# Power.net
KiCad netlist of a schematic drawn in Altium Designer
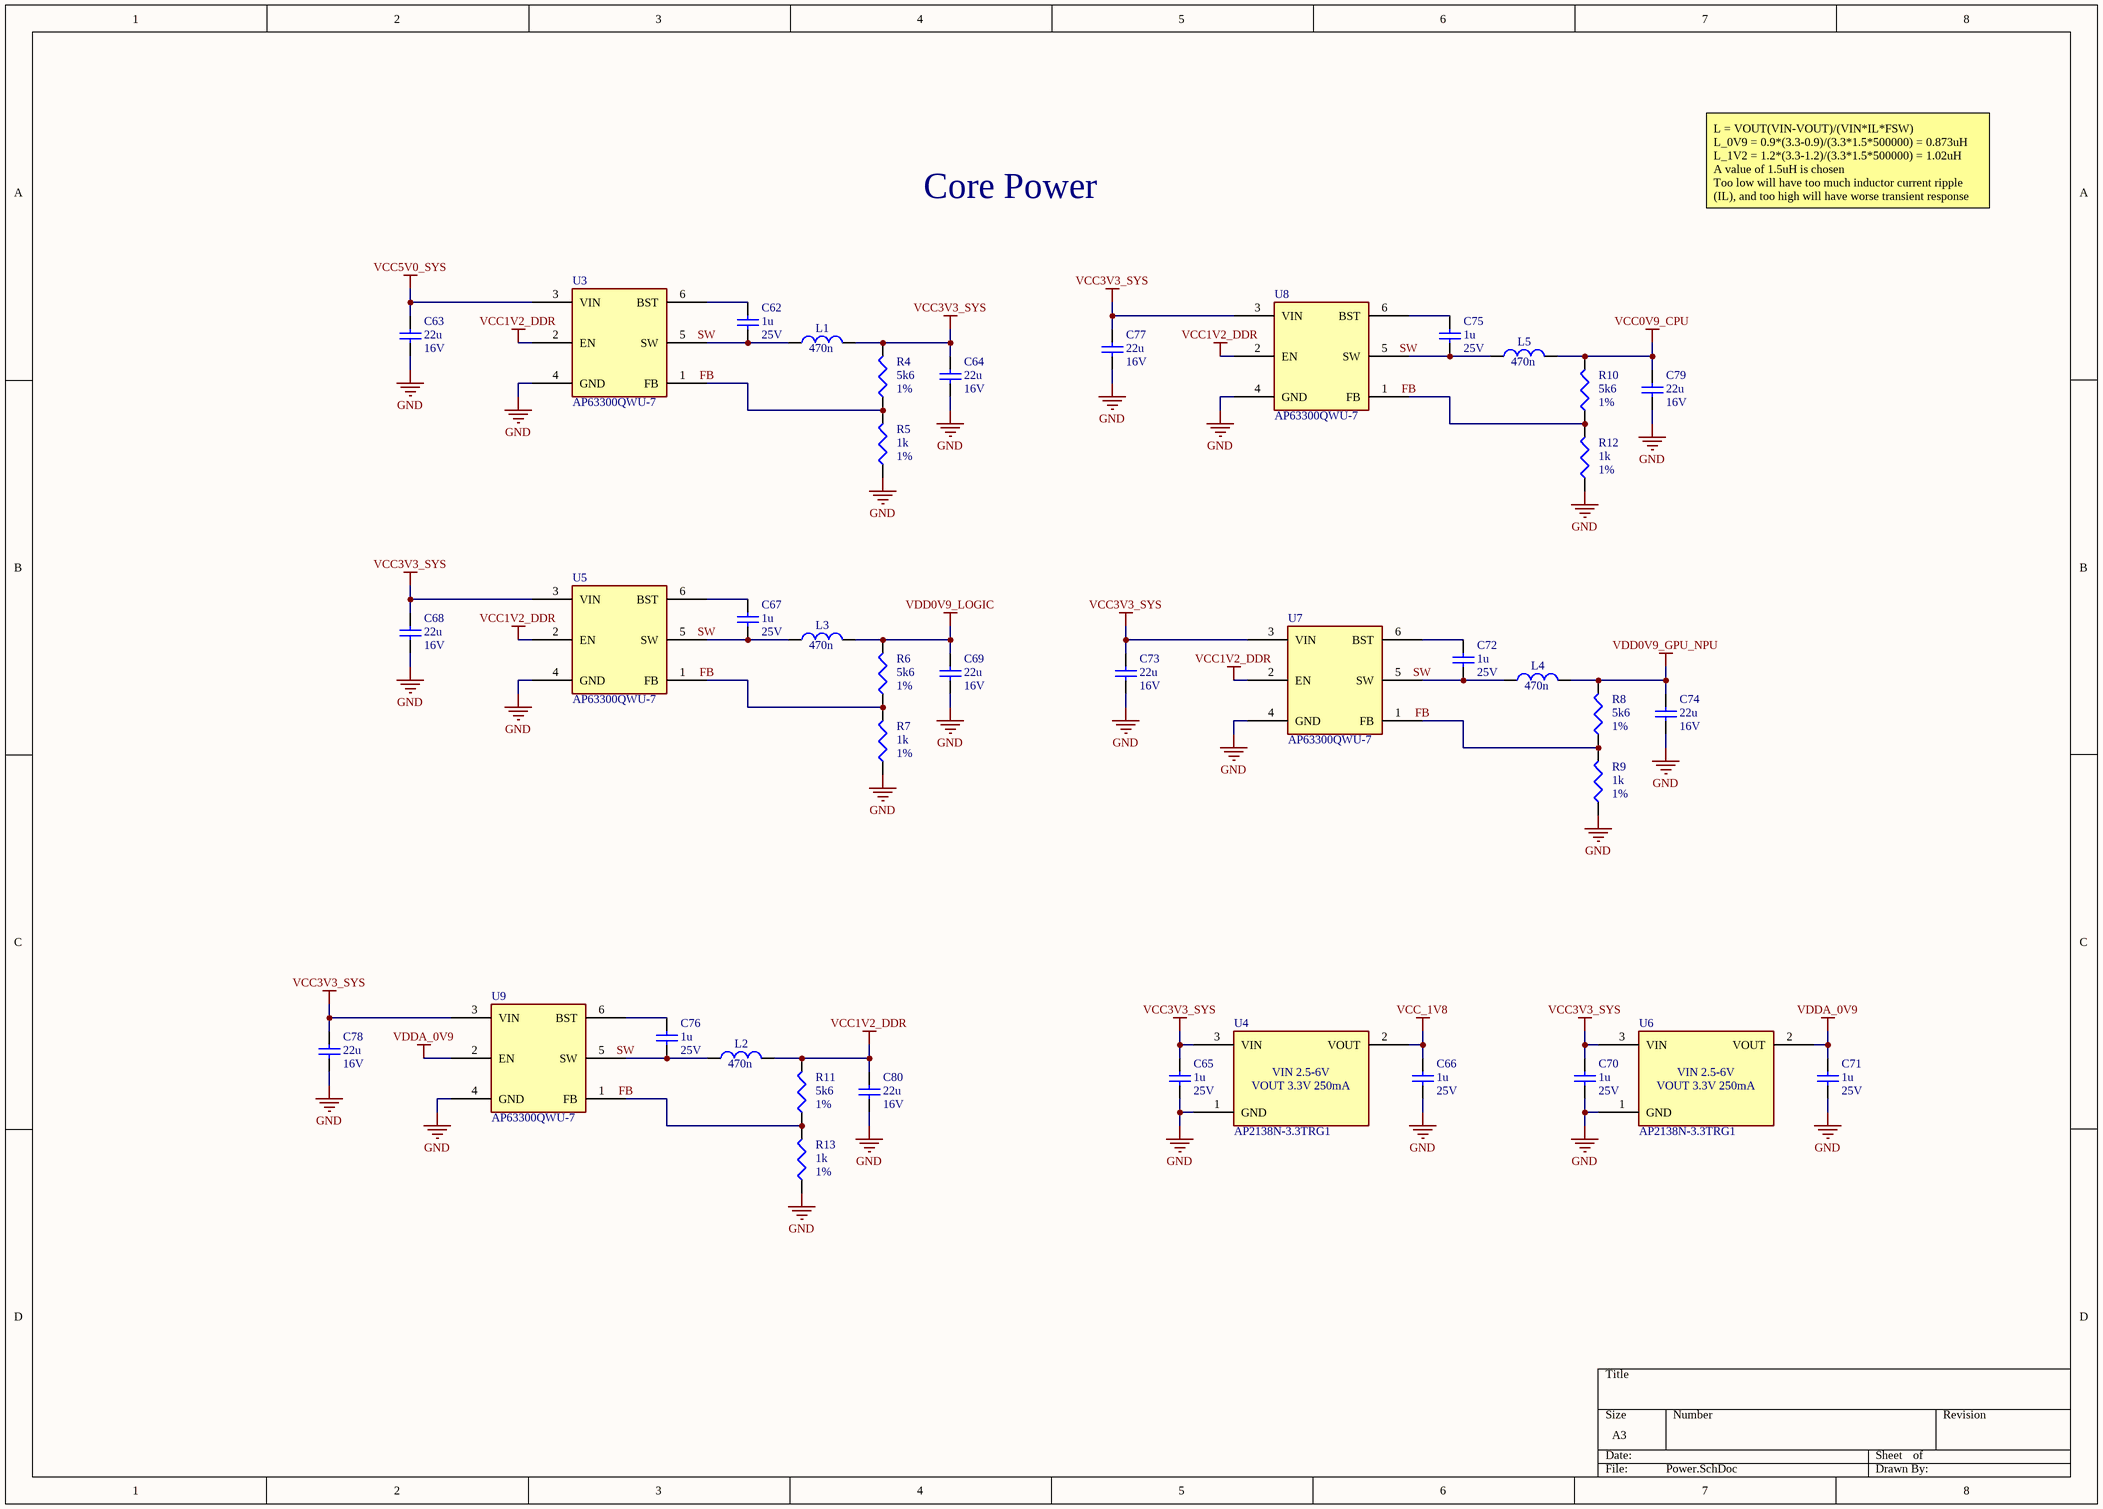
[diagram p0: Power.SchDoc]

(export (version "E")
  (design (tool "Eeschema 10.0.6"))
  (components
    (comp (ref "C62")
      (value "1u")
      (footprint "GRM155R61E105KA12D")
      (description "CAP 1U 25V X5R 0402")
      (fields (field (name "VOLTAGE") "25V") (field (name "Comment") "GRM155R61E105KA12D"))
      (libsource (lib "PersonalAltiumLibrary") (part "GRM155R61E105KA12D"))
    )
    (comp (ref "C63")
      (value "22u")
      (footprint "GRM188R61C226ME01D")
      (description "CAP 22U 16V X5R 0603")
      (fields (field (name "VOLTAGE") "16V") (field (name "Comment") "GRM188R61C226ME01D"))
      (libsource (lib "PersonalAltiumLibrary") (part "GRM188R61C226ME01D"))
    )
    (comp (ref "C64")
      (value "22u")
      (footprint "GRM188R61C226ME01D")
      (description "CAP 22U 16V X5R 0603")
      (fields (field (name "VOLTAGE") "16V") (field (name "Comment") "GRM188R61C226ME01D"))
      (libsource (lib "PersonalAltiumLibrary") (part "GRM188R61C226ME01D"))
    )
    (comp (ref "C65")
      (value "1u")
      (footprint "GRM155R61E105KA12D")
      (description "CAP 1U 25V X5R 0402")
      (fields (field (name "VOLTAGE") "25V") (field (name "Comment") "GRM155R61E105KA12D"))
      (libsource (lib "PersonalAltiumLibrary") (part "GRM155R61E105KA12D"))
    )
    (comp (ref "C66")
      (value "1u")
      (footprint "GRM155R61E105KA12D")
      (description "CAP 1U 25V X5R 0402")
      (fields (field (name "VOLTAGE") "25V") (field (name "Comment") "GRM155R61E105KA12D"))
      (libsource (lib "PersonalAltiumLibrary") (part "GRM155R61E105KA12D"))
    )
    (comp (ref "C67")
      (value "1u")
      (footprint "GRM155R61E105KA12D")
      (description "CAP 1U 25V X5R 0402")
      (fields (field (name "VOLTAGE") "25V") (field (name "Comment") "GRM155R61E105KA12D"))
      (libsource (lib "PersonalAltiumLibrary") (part "GRM155R61E105KA12D"))
    )
    (comp (ref "C68")
      (value "22u")
      (footprint "GRM188R61C226ME01D")
      (description "CAP 22U 16V X5R 0603")
      (fields (field (name "VOLTAGE") "16V") (field (name "Comment") "GRM188R61C226ME01D"))
      (libsource (lib "PersonalAltiumLibrary") (part "GRM188R61C226ME01D"))
    )
    (comp (ref "C69")
      (value "22u")
      (footprint "GRM188R61C226ME01D")
      (description "CAP 22U 16V X5R 0603")
      (fields (field (name "VOLTAGE") "16V") (field (name "Comment") "GRM188R61C226ME01D"))
      (libsource (lib "PersonalAltiumLibrary") (part "GRM188R61C226ME01D"))
    )
    (comp (ref "C70")
      (value "1u")
      (footprint "GRM155R61E105KA12D")
      (description "CAP 1U 25V X5R 0402")
      (fields (field (name "VOLTAGE") "25V") (field (name "Comment") "GRM155R61E105KA12D"))
      (libsource (lib "PersonalAltiumLibrary") (part "GRM155R61E105KA12D"))
    )
    (comp (ref "C71")
      (value "1u")
      (footprint "GRM155R61E105KA12D")
      (description "CAP 1U 25V X5R 0402")
      (fields (field (name "VOLTAGE") "25V") (field (name "Comment") "GRM155R61E105KA12D"))
      (libsource (lib "PersonalAltiumLibrary") (part "GRM155R61E105KA12D"))
    )
    (comp (ref "C72")
      (value "1u")
      (footprint "GRM155R61E105KA12D")
      (description "CAP 1U 25V X5R 0402")
      (fields (field (name "VOLTAGE") "25V") (field (name "Comment") "GRM155R61E105KA12D"))
      (libsource (lib "PersonalAltiumLibrary") (part "GRM155R61E105KA12D"))
    )
    (comp (ref "C73")
      (value "22u")
      (footprint "GRM188R61C226ME01D")
      (description "CAP 22U 16V X5R 0603")
      (fields (field (name "VOLTAGE") "16V") (field (name "Comment") "GRM188R61C226ME01D"))
      (libsource (lib "PersonalAltiumLibrary") (part "GRM188R61C226ME01D"))
    )
    (comp (ref "C74")
      (value "22u")
      (footprint "GRM188R61C226ME01D")
      (description "CAP 22U 16V X5R 0603")
      (fields (field (name "VOLTAGE") "16V") (field (name "Comment") "GRM188R61C226ME01D"))
      (libsource (lib "PersonalAltiumLibrary") (part "GRM188R61C226ME01D"))
    )
    (comp (ref "C75")
      (value "1u")
      (footprint "GRM155R61E105KA12D")
      (description "CAP 1U 25V X5R 0402")
      (fields (field (name "VOLTAGE") "25V") (field (name "Comment") "GRM155R61E105KA12D"))
      (libsource (lib "PersonalAltiumLibrary") (part "GRM155R61E105KA12D"))
    )
    (comp (ref "C76")
      (value "1u")
      (footprint "GRM155R61E105KA12D")
      (description "CAP 1U 25V X5R 0402")
      (fields (field (name "VOLTAGE") "25V") (field (name "Comment") "GRM155R61E105KA12D"))
      (libsource (lib "PersonalAltiumLibrary") (part "GRM155R61E105KA12D"))
    )
    (comp (ref "C77")
      (value "22u")
      (footprint "GRM188R61C226ME01D")
      (description "CAP 22U 16V X5R 0603")
      (fields (field (name "VOLTAGE") "16V") (field (name "Comment") "GRM188R61C226ME01D"))
      (libsource (lib "PersonalAltiumLibrary") (part "GRM188R61C226ME01D"))
    )
    (comp (ref "C78")
      (value "22u")
      (footprint "GRM188R61C226ME01D")
      (description "CAP 22U 16V X5R 0603")
      (fields (field (name "VOLTAGE") "16V") (field (name "Comment") "GRM188R61C226ME01D"))
      (libsource (lib "PersonalAltiumLibrary") (part "GRM188R61C226ME01D"))
    )
    (comp (ref "C79")
      (value "22u")
      (footprint "GRM188R61C226ME01D")
      (description "CAP 22U 16V X5R 0603")
      (fields (field (name "VOLTAGE") "16V") (field (name "Comment") "GRM188R61C226ME01D"))
      (libsource (lib "PersonalAltiumLibrary") (part "GRM188R61C226ME01D"))
    )
    (comp (ref "C80")
      (value "22u")
      (footprint "GRM188R61C226ME01D")
      (description "CAP 22U 16V X5R 0603")
      (fields (field (name "VOLTAGE") "16V") (field (name "Comment") "GRM188R61C226ME01D"))
      (libsource (lib "PersonalAltiumLibrary") (part "GRM188R61C226ME01D"))
    )
    (comp (ref "L1")
      (value "470n")
      (footprint "DFE322520FD-1R5M")
      (description "IND 1.5U 6A 1210")
      (fields (field (name "Comment") "DFE322520FD-1R5M"))
      (libsource (lib "PersonalAltiumLibrary") (part "DFE322520FD-1R5M"))
    )
    (comp (ref "L2")
      (value "470n")
      (footprint "DFE322520FD-1R5M")
      (description "IND 1.5U 6A 1210")
      (fields (field (name "Comment") "DFE322520FD-1R5M"))
      (libsource (lib "PersonalAltiumLibrary") (part "DFE322520FD-1R5M"))
    )
    (comp (ref "L3")
      (value "470n")
      (footprint "DFE322520FD-1R5M")
      (description "IND 1.5U 6A 1210")
      (fields (field (name "Comment") "DFE322520FD-1R5M"))
      (libsource (lib "PersonalAltiumLibrary") (part "DFE322520FD-1R5M"))
    )
    (comp (ref "L4")
      (value "470n")
      (footprint "DFE322520FD-1R5M")
      (description "IND 1.5U 6A 1210")
      (fields (field (name "Comment") "DFE322520FD-1R5M"))
      (libsource (lib "PersonalAltiumLibrary") (part "DFE322520FD-1R5M"))
    )
    (comp (ref "L5")
      (value "470n")
      (footprint "DFE322520FD-1R5M")
      (description "IND 1.5U 6A 1210")
      (fields (field (name "Comment") "DFE322520FD-1R5M"))
      (libsource (lib "PersonalAltiumLibrary") (part "DFE322520FD-1R5M"))
    )
    (comp (ref "R4")
      (value "5k6")
      (footprint "RC0402FR-075K6L")
      (description "RES 5.6k 1% 62.5mW 0402")
      (fields (field (name "TOLERANCE") "1%") (field (name "Comment") "RC0402FR-075K6L"))
      (libsource (lib "PersonalAltiumLibrary") (part "RC0402FR-075K6L"))
    )
    (comp (ref "R5")
      (value "1k")
      (footprint "RC0402FR-071KL")
      (description "RES 1k 1% 62.5mW 0402")
      (fields (field (name "TOLERANCE") "1%") (field (name "Comment") "RC0402FR-071KL"))
      (libsource (lib "PersonalAltiumLibrary") (part "RC0402FR-071KL"))
    )
    (comp (ref "R6")
      (value "5k6")
      (footprint "RC0402FR-075K6L")
      (description "RES 5.6k 1% 62.5mW 0402")
      (fields (field (name "TOLERANCE") "1%") (field (name "Comment") "RC0402FR-075K6L"))
      (libsource (lib "PersonalAltiumLibrary") (part "RC0402FR-075K6L"))
    )
    (comp (ref "R7")
      (value "1k")
      (footprint "RC0402FR-071KL")
      (description "RES 1k 1% 62.5mW 0402")
      (fields (field (name "TOLERANCE") "1%") (field (name "Comment") "RC0402FR-071KL"))
      (libsource (lib "PersonalAltiumLibrary") (part "RC0402FR-071KL"))
    )
    (comp (ref "R8")
      (value "5k6")
      (footprint "RC0402FR-075K6L")
      (description "RES 5.6k 1% 62.5mW 0402")
      (fields (field (name "TOLERANCE") "1%") (field (name "Comment") "RC0402FR-075K6L"))
      (libsource (lib "PersonalAltiumLibrary") (part "RC0402FR-075K6L"))
    )
    (comp (ref "R9")
      (value "1k")
      (footprint "RC0402FR-071KL")
      (description "RES 1k 1% 62.5mW 0402")
      (fields (field (name "TOLERANCE") "1%") (field (name "Comment") "RC0402FR-071KL"))
      (libsource (lib "PersonalAltiumLibrary") (part "RC0402FR-071KL"))
    )
    (comp (ref "R10")
      (value "5k6")
      (footprint "RC0402FR-075K6L")
      (description "RES 5.6k 1% 62.5mW 0402")
      (fields (field (name "TOLERANCE") "1%") (field (name "Comment") "RC0402FR-075K6L"))
      (libsource (lib "PersonalAltiumLibrary") (part "RC0402FR-075K6L"))
    )
    (comp (ref "R11")
      (value "5k6")
      (footprint "RC0402FR-075K6L")
      (description "RES 5.6k 1% 62.5mW 0402")
      (fields (field (name "TOLERANCE") "1%") (field (name "Comment") "RC0402FR-075K6L"))
      (libsource (lib "PersonalAltiumLibrary") (part "RC0402FR-075K6L"))
    )
    (comp (ref "R12")
      (value "1k")
      (footprint "RC0402FR-071KL")
      (description "RES 1k 1% 62.5mW 0402")
      (fields (field (name "TOLERANCE") "1%") (field (name "Comment") "RC0402FR-071KL"))
      (libsource (lib "PersonalAltiumLibrary") (part "RC0402FR-071KL"))
    )
    (comp (ref "R13")
      (value "1k")
      (footprint "RC0402FR-071KL")
      (description "RES 1k 1% 62.5mW 0402")
      (fields (field (name "TOLERANCE") "1%") (field (name "Comment") "RC0402FR-071KL"))
      (libsource (lib "PersonalAltiumLibrary") (part "RC0402FR-071KL"))
    )
    (comp (ref "U3")
      (value "AP63300QWU-7")
      (footprint "AP63300QWU-7")
      (description "BUCK 3A")
      (libsource (lib "PersonalAltiumLibrary") (part "AP63300QWU-7"))
    )
    (comp (ref "U4")
      (value "AP2138N-3.3TRG1")
      (footprint "AP2138N-3.3TRG1")
      (description "LDO 3.3V 250mA")
      (libsource (lib "PersonalAltiumLibrary") (part "AP2138N-3.3TRG1"))
    )
    (comp (ref "U5")
      (value "AP63300QWU-7")
      (footprint "AP63300QWU-7")
      (description "BUCK 3A")
      (libsource (lib "PersonalAltiumLibrary") (part "AP63300QWU-7"))
    )
    (comp (ref "U6")
      (value "AP2138N-3.3TRG1")
      (footprint "AP2138N-3.3TRG1")
      (description "LDO 3.3V 250mA")
      (libsource (lib "PersonalAltiumLibrary") (part "AP2138N-3.3TRG1"))
    )
    (comp (ref "U7")
      (value "AP63300QWU-7")
      (footprint "AP63300QWU-7")
      (description "BUCK 3A")
      (libsource (lib "PersonalAltiumLibrary") (part "AP63300QWU-7"))
    )
    (comp (ref "U8")
      (value "AP63300QWU-7")
      (footprint "AP63300QWU-7")
      (description "BUCK 3A")
      (libsource (lib "PersonalAltiumLibrary") (part "AP63300QWU-7"))
    )
    (comp (ref "U9")
      (value "AP63300QWU-7")
      (footprint "AP63300QWU-7")
      (description "BUCK 3A")
      (libsource (lib "PersonalAltiumLibrary") (part "AP63300QWU-7"))
    )
  )
  (nets
    (net (code "1") (name "/FB") (class "Default")
      (node (ref "R10") (pin "2") (pinfunction "2_2") (pintype "passive"))
      (node (ref "R11") (pin "2") (pinfunction "2_2") (pintype "passive"))
      (node (ref "R12") (pin "1") (pinfunction "1_1") (pintype "passive"))
      (node (ref "R13") (pin "1") (pinfunction "1_1") (pintype "passive"))
      (node (ref "R4") (pin "2") (pinfunction "2_2") (pintype "passive"))
      (node (ref "R5") (pin "1") (pinfunction "1_1") (pintype "passive"))
      (node (ref "R6") (pin "2") (pinfunction "2_2") (pintype "passive"))
      (node (ref "R7") (pin "1") (pinfunction "1_1") (pintype "passive"))
      (node (ref "R8") (pin "2") (pinfunction "2_2") (pintype "passive"))
      (node (ref "R9") (pin "1") (pinfunction "1_1") (pintype "passive"))
      (node (ref "U3") (pin "1") (pinfunction "FB_1") (pintype "passive"))
      (node (ref "U5") (pin "1") (pinfunction "FB_1") (pintype "passive"))
      (node (ref "U7") (pin "1") (pinfunction "FB_1") (pintype "passive"))
      (node (ref "U8") (pin "1") (pinfunction "FB_1") (pintype "passive"))
      (node (ref "U9") (pin "1") (pinfunction "FB_1") (pintype "passive"))
    )
    (net (code "2") (name "/SW") (class "Default")
      (node (ref "C62") (pin "2") (pinfunction "2_2") (pintype "passive"))
      (node (ref "C67") (pin "2") (pinfunction "2_2") (pintype "passive"))
      (node (ref "C72") (pin "2") (pinfunction "2_2") (pintype "passive"))
      (node (ref "C75") (pin "2") (pinfunction "2_2") (pintype "passive"))
      (node (ref "C76") (pin "2") (pinfunction "2_2") (pintype "passive"))
      (node (ref "L1") (pin "1") (pinfunction "1_1") (pintype "passive"))
      (node (ref "L2") (pin "1") (pinfunction "1_1") (pintype "passive"))
      (node (ref "L3") (pin "1") (pinfunction "1_1") (pintype "passive"))
      (node (ref "L4") (pin "1") (pinfunction "1_1") (pintype "passive"))
      (node (ref "L5") (pin "1") (pinfunction "1_1") (pintype "passive"))
      (node (ref "U3") (pin "5") (pinfunction "SW_5") (pintype "passive"))
      (node (ref "U5") (pin "5") (pinfunction "SW_5") (pintype "passive"))
      (node (ref "U7") (pin "5") (pinfunction "SW_5") (pintype "passive"))
      (node (ref "U8") (pin "5") (pinfunction "SW_5") (pintype "passive"))
      (node (ref "U9") (pin "5") (pinfunction "SW_5") (pintype "passive"))
    )
    (net (code "3") (name "GND") (class "Default")
      (node (ref "C63") (pin "2") (pinfunction "2_2") (pintype "passive"))
      (node (ref "C64") (pin "2") (pinfunction "2_2") (pintype "passive"))
      (node (ref "C65") (pin "2") (pinfunction "2_2") (pintype "passive"))
      (node (ref "C66") (pin "2") (pinfunction "2_2") (pintype "passive"))
      (node (ref "C68") (pin "2") (pinfunction "2_2") (pintype "passive"))
      (node (ref "C69") (pin "2") (pinfunction "2_2") (pintype "passive"))
      (node (ref "C70") (pin "2") (pinfunction "2_2") (pintype "passive"))
      (node (ref "C71") (pin "2") (pinfunction "2_2") (pintype "passive"))
      (node (ref "C73") (pin "2") (pinfunction "2_2") (pintype "passive"))
      (node (ref "C74") (pin "2") (pinfunction "2_2") (pintype "passive"))
      (node (ref "C77") (pin "2") (pinfunction "2_2") (pintype "passive"))
      (node (ref "C78") (pin "2") (pinfunction "2_2") (pintype "passive"))
      (node (ref "C79") (pin "2") (pinfunction "2_2") (pintype "passive"))
      (node (ref "C80") (pin "2") (pinfunction "2_2") (pintype "passive"))
      (node (ref "R12") (pin "2") (pinfunction "2_2") (pintype "passive"))
      (node (ref "R13") (pin "2") (pinfunction "2_2") (pintype "passive"))
      (node (ref "R5") (pin "2") (pinfunction "2_2") (pintype "passive"))
      (node (ref "R7") (pin "2") (pinfunction "2_2") (pintype "passive"))
      (node (ref "R9") (pin "2") (pinfunction "2_2") (pintype "passive"))
      (node (ref "U3") (pin "4") (pinfunction "GND_4") (pintype "passive"))
      (node (ref "U4") (pin "1") (pinfunction "GND_1") (pintype "passive"))
      (node (ref "U5") (pin "4") (pinfunction "GND_4") (pintype "passive"))
      (node (ref "U6") (pin "1") (pinfunction "GND_1") (pintype "passive"))
      (node (ref "U7") (pin "4") (pinfunction "GND_4") (pintype "passive"))
      (node (ref "U8") (pin "4") (pinfunction "GND_4") (pintype "passive"))
      (node (ref "U9") (pin "4") (pinfunction "GND_4") (pintype "passive"))
    )
    (net (code "4") (name "Net-(U3-BST)") (class "Default")
      (node (ref "C62") (pin "1") (pinfunction "1_1") (pintype "passive"))
      (node (ref "U3") (pin "6") (pinfunction "BST_6") (pintype "passive"))
    )
    (net (code "5") (name "Net-(U5-BST)") (class "Default")
      (node (ref "C67") (pin "1") (pinfunction "1_1") (pintype "passive"))
      (node (ref "U5") (pin "6") (pinfunction "BST_6") (pintype "passive"))
    )
    (net (code "6") (name "Net-(U7-BST)") (class "Default")
      (node (ref "C72") (pin "1") (pinfunction "1_1") (pintype "passive"))
      (node (ref "U7") (pin "6") (pinfunction "BST_6") (pintype "passive"))
    )
    (net (code "7") (name "Net-(U8-BST)") (class "Default")
      (node (ref "C75") (pin "1") (pinfunction "1_1") (pintype "passive"))
      (node (ref "U8") (pin "6") (pinfunction "BST_6") (pintype "passive"))
    )
    (net (code "8") (name "Net-(U9-BST)") (class "Default")
      (node (ref "C76") (pin "1") (pinfunction "1_1") (pintype "passive"))
      (node (ref "U9") (pin "6") (pinfunction "BST_6") (pintype "passive"))
    )
    (net (code "9") (name "VCC0V9_CPU") (class "Default")
      (node (ref "C79") (pin "1") (pinfunction "1_1") (pintype "passive"))
      (node (ref "L5") (pin "2") (pinfunction "2_2") (pintype "passive"))
      (node (ref "R10") (pin "1") (pinfunction "1_1") (pintype "passive"))
    )
    (net (code "10") (name "VCC1V2_DDR") (class "Default")
      (node (ref "C80") (pin "1") (pinfunction "1_1") (pintype "passive"))
      (node (ref "L2") (pin "2") (pinfunction "2_2") (pintype "passive"))
      (node (ref "R11") (pin "1") (pinfunction "1_1") (pintype "passive"))
      (node (ref "U3") (pin "2") (pinfunction "EN_2") (pintype "passive"))
      (node (ref "U5") (pin "2") (pinfunction "EN_2") (pintype "passive"))
      (node (ref "U7") (pin "2") (pinfunction "EN_2") (pintype "passive"))
      (node (ref "U8") (pin "2") (pinfunction "EN_2") (pintype "passive"))
    )
    (net (code "11") (name "VCC3V3_SYS") (class "Default")
      (node (ref "C64") (pin "1") (pinfunction "1_1") (pintype "passive"))
      (node (ref "C65") (pin "1") (pinfunction "1_1") (pintype "passive"))
      (node (ref "C68") (pin "1") (pinfunction "1_1") (pintype "passive"))
      (node (ref "C70") (pin "1") (pinfunction "1_1") (pintype "passive"))
      (node (ref "C73") (pin "1") (pinfunction "1_1") (pintype "passive"))
      (node (ref "C77") (pin "1") (pinfunction "1_1") (pintype "passive"))
      (node (ref "C78") (pin "1") (pinfunction "1_1") (pintype "passive"))
      (node (ref "L1") (pin "2") (pinfunction "2_2") (pintype "passive"))
      (node (ref "R4") (pin "1") (pinfunction "1_1") (pintype "passive"))
      (node (ref "U4") (pin "3") (pinfunction "VIN_3") (pintype "passive"))
      (node (ref "U5") (pin "3") (pinfunction "VIN_3") (pintype "passive"))
      (node (ref "U6") (pin "3") (pinfunction "VIN_3") (pintype "passive"))
      (node (ref "U7") (pin "3") (pinfunction "VIN_3") (pintype "passive"))
      (node (ref "U8") (pin "3") (pinfunction "VIN_3") (pintype "passive"))
      (node (ref "U9") (pin "3") (pinfunction "VIN_3") (pintype "passive"))
    )
    (net (code "12") (name "VCC5V0_SYS") (class "Default")
      (node (ref "C63") (pin "1") (pinfunction "1_1") (pintype "passive"))
      (node (ref "U3") (pin "3") (pinfunction "VIN_3") (pintype "passive"))
    )
    (net (code "13") (name "VCC_1V8") (class "Default")
      (node (ref "C66") (pin "1") (pinfunction "1_1") (pintype "passive"))
      (node (ref "U4") (pin "2") (pinfunction "VOUT_2") (pintype "passive"))
    )
    (net (code "14") (name "VDD0V9_GPU_NPU") (class "Default")
      (node (ref "C74") (pin "1") (pinfunction "1_1") (pintype "passive"))
      (node (ref "L4") (pin "2") (pinfunction "2_2") (pintype "passive"))
      (node (ref "R8") (pin "1") (pinfunction "1_1") (pintype "passive"))
    )
    (net (code "15") (name "VDD0V9_LOGIC") (class "Default")
      (node (ref "C69") (pin "1") (pinfunction "1_1") (pintype "passive"))
      (node (ref "L3") (pin "2") (pinfunction "2_2") (pintype "passive"))
      (node (ref "R6") (pin "1") (pinfunction "1_1") (pintype "passive"))
    )
    (net (code "16") (name "VDDA_0V9") (class "Default")
      (node (ref "C71") (pin "1") (pinfunction "1_1") (pintype "passive"))
      (node (ref "U6") (pin "2") (pinfunction "VOUT_2") (pintype "passive"))
      (node (ref "U9") (pin "2") (pinfunction "EN_2") (pintype "passive"))
    )
  )
)
